# 2019_Dashboard_1-28-19.net
KiCad netlist of a schematic drawn in EAGLE
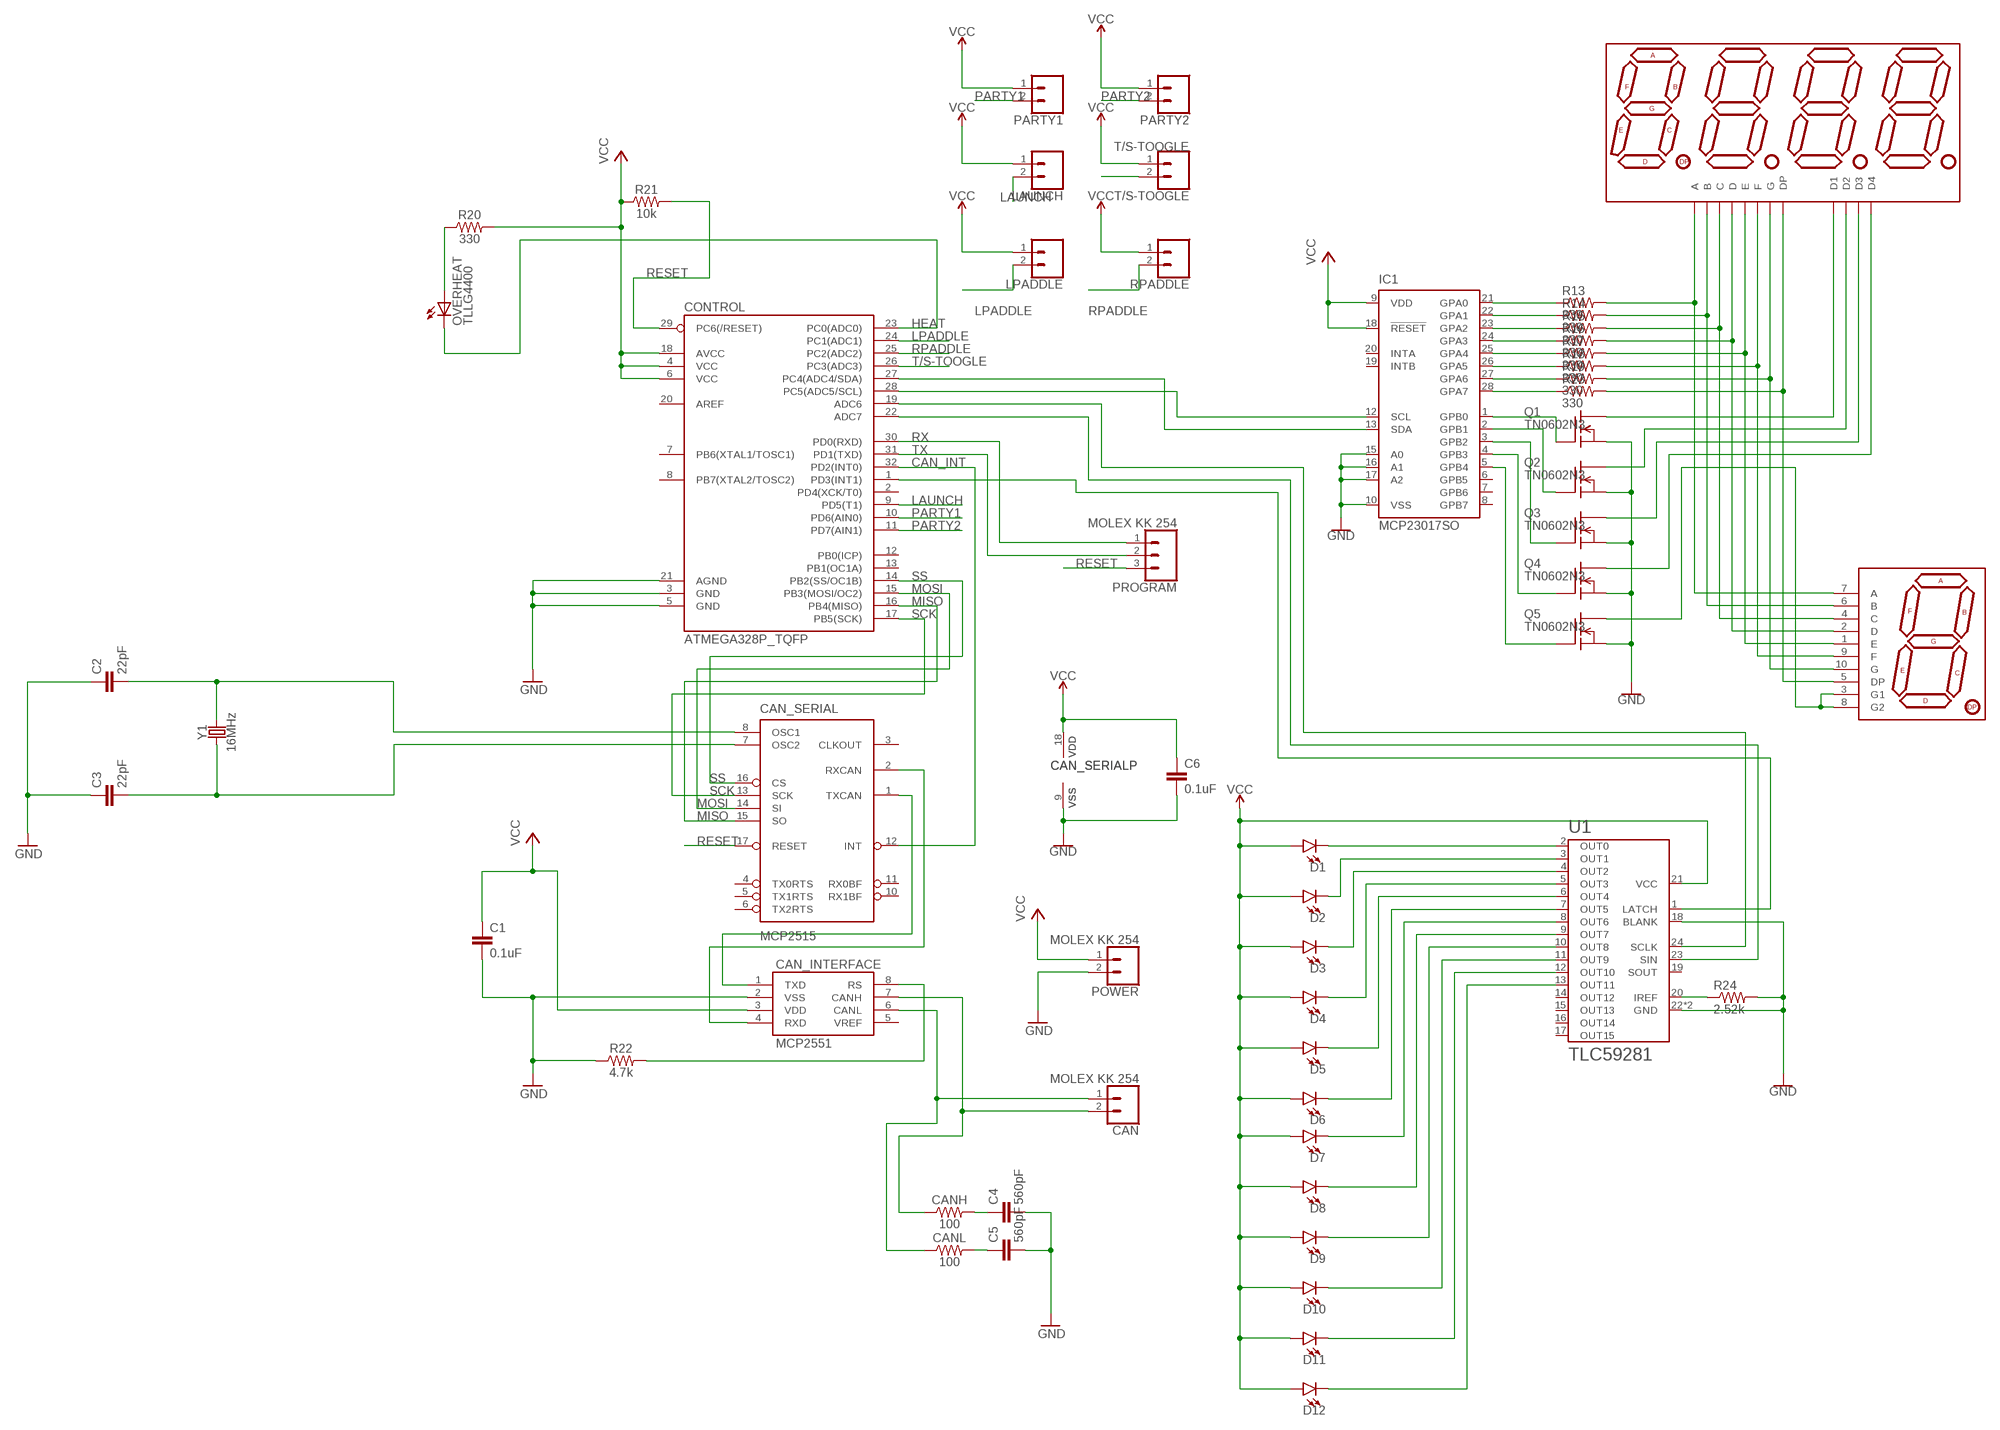
[diagram p0: schematic, sheet 1]

(export (version "E")
  (design (tool "Eeschema 10.0.6"))
  (components
    (comp (ref "C1")
      (value "0.1uF")
      (footprint "eagle-import:0603")
      (libsource (lib "eagle-import") (part "0.1UF-0603-25V-(+80/-20%)"))
    )
    (comp (ref "C2")
      (value "22pF")
      (footprint "eagle-import:0603")
      (libsource (lib "eagle-import") (part "22PF-0603-50V-5%"))
    )
    (comp (ref "C3")
      (value "22pF")
      (footprint "eagle-import:0603")
      (libsource (lib "eagle-import") (part "22PF-0603-50V-5%"))
    )
    (comp (ref "C4")
      (value "560pF")
      (footprint "eagle-import:0603")
      (libsource (lib "eagle-import") (part "560PF-0603-50V-5%"))
    )
    (comp (ref "C5")
      (value "560pF")
      (footprint "eagle-import:0603")
      (libsource (lib "eagle-import") (part "560PF-0603-50V-5%"))
    )
    (comp (ref "C6")
      (value "0.1uF")
      (footprint "eagle-import:0402")
      (libsource (lib "eagle-import") (part "0.1UF-0402-16V-10%"))
    )
    (comp (ref "CAN")
      (value "MOLEX KK 254")
      (footprint "eagle-import:1X02")
      (libsource (lib "eagle-import") (part "CONN_02"))
    )
    (comp (ref "CANH")
      (value "100")
      (footprint "eagle-import:0603")
      (libsource (lib "eagle-import") (part "100OHM-0603-1/4W-5%"))
    )
    (comp (ref "CANL")
      (value "100")
      (footprint "eagle-import:0603")
      (libsource (lib "eagle-import") (part "100OHM-0603-1/4W-5%"))
    )
    (comp (ref "CAN_INTERFACE")
      (value "MCP2551")
      (footprint "eagle-import:SO08")
      (libsource (lib "eagle-import") (part "MCP2551"))
    )
    (comp (ref "CAN_SERIAL")
      (value "MCP2515")
      (footprint "eagle-import:SO18W")
      (libsource (lib "eagle-import") (part "MCP2515(MCP2510)SO"))
    )
    (comp (ref "CONTROL")
      (value "ATMEGA328P_TQFP")
      (footprint "eagle-import:TQFP32-08")
      (libsource (lib "eagle-import") (part "ATMEGA328P_TQFP"))
    )
    (comp (ref "D1")
      (value "LED5MM")
      (footprint "eagle-import:LED_5MM")
      (libsource (lib "eagle-import") (part "LED5MM"))
    )
    (comp (ref "D2")
      (value "LED5MM")
      (footprint "eagle-import:LED_5MM")
      (libsource (lib "eagle-import") (part "LED5MM"))
    )
    (comp (ref "D3")
      (value "LED5MM")
      (footprint "eagle-import:LED_5MM")
      (libsource (lib "eagle-import") (part "LED5MM"))
    )
    (comp (ref "D4")
      (value "LED5MM")
      (footprint "eagle-import:LED_5MM")
      (libsource (lib "eagle-import") (part "LED5MM"))
    )
    (comp (ref "D5")
      (value "LED5MM")
      (footprint "eagle-import:LED_5MM")
      (libsource (lib "eagle-import") (part "LED5MM"))
    )
    (comp (ref "D6")
      (value "LED5MM")
      (footprint "eagle-import:LED_5MM")
      (libsource (lib "eagle-import") (part "LED5MM"))
    )
    (comp (ref "D7")
      (value "LED5MM")
      (footprint "eagle-import:LED_5MM")
      (libsource (lib "eagle-import") (part "LED5MM"))
    )
    (comp (ref "D8")
      (value "LED5MM")
      (footprint "eagle-import:LED_5MM")
      (libsource (lib "eagle-import") (part "LED5MM"))
    )
    (comp (ref "D9")
      (value "LED5MM")
      (footprint "eagle-import:LED_5MM")
      (libsource (lib "eagle-import") (part "LED5MM"))
    )
    (comp (ref "D10")
      (value "LED5MM")
      (footprint "eagle-import:LED_5MM")
      (libsource (lib "eagle-import") (part "LED5MM"))
    )
    (comp (ref "D11")
      (value "LED5MM")
      (footprint "eagle-import:LED_5MM")
      (libsource (lib "eagle-import") (part "LED5MM"))
    )
    (comp (ref "D12")
      (value "LED5MM")
      (footprint "eagle-import:LED_5MM")
      (libsource (lib "eagle-import") (part "LED5MM"))
    )
    (comp (ref "DISP1")
      (value "ATA8041ARBJ")
      (footprint "eagle-import:7-SEGMENT-4DIGIT-20MM")
      (libsource (lib "eagle-import") (part "7-SEGMENT-4DIGIT-20MM-RED"))
    )
    (comp (ref "IC1")
      (value "MCP23017SO")
      (footprint "eagle-import:SO28W")
      (libsource (lib "eagle-import") (part "MCP23017SO"))
    )
    (comp (ref "LAUNCH")
      (value "CONN_02LOCK")
      (footprint "eagle-import:1X02_LOCK")
      (libsource (lib "eagle-import") (part "CONN_02LOCK"))
    )
    (comp (ref "LPADDLE")
      (value "CONN_02LOCK")
      (footprint "eagle-import:1X02_LOCK")
      (libsource (lib "eagle-import") (part "CONN_02LOCK"))
    )
    (comp (ref "OVERHEAT")
      (value "TLLG4400")
      (footprint "eagle-import:LED3MM")
      (fields (field (name "MF") "VISHAY SEMICONDUCTOR"))
      (libsource (lib "eagle-import") (part "TLLG4400"))
    )
    (comp (ref "PARTY1")
      (value "CONN_02LOCK")
      (footprint "eagle-import:1X02_LOCK")
      (libsource (lib "eagle-import") (part "CONN_02LOCK"))
    )
    (comp (ref "PARTY2")
      (value "CONN_02LOCK")
      (footprint "eagle-import:1X02_LOCK")
      (libsource (lib "eagle-import") (part "CONN_02LOCK"))
    )
    (comp (ref "POWER")
      (value "MOLEX KK 254")
      (footprint "eagle-import:1X02")
      (libsource (lib "eagle-import") (part "CONN_02"))
    )
    (comp (ref "PROGRAM")
      (value "MOLEX KK 254")
      (footprint "eagle-import:1X03")
      (libsource (lib "eagle-import") (part "CONN_03"))
    )
    (comp (ref "Q1")
      (value "TN0602N3")
      (footprint "eagle-import:TO-92")
      (libsource (lib "eagle-import") (part "TN0602N3"))
    )
    (comp (ref "Q2")
      (value "TN0602N3")
      (footprint "eagle-import:TO-92")
      (libsource (lib "eagle-import") (part "TN0602N3"))
    )
    (comp (ref "Q3")
      (value "TN0602N3")
      (footprint "eagle-import:TO-92")
      (libsource (lib "eagle-import") (part "TN0602N3"))
    )
    (comp (ref "Q4")
      (value "TN0602N3")
      (footprint "eagle-import:TO-92")
      (libsource (lib "eagle-import") (part "TN0602N3"))
    )
    (comp (ref "Q5")
      (value "TN0602N3")
      (footprint "eagle-import:TO-92")
      (libsource (lib "eagle-import") (part "TN0602N3"))
    )
    (comp (ref "R13")
      (value "330")
      (footprint "eagle-import:R0603")
      (libsource (lib "eagle-import") (part "R-US_R0603"))
    )
    (comp (ref "R14")
      (value "330")
      (footprint "eagle-import:R0603")
      (libsource (lib "eagle-import") (part "R-US_R0603"))
    )
    (comp (ref "R15")
      (value "330")
      (footprint "eagle-import:R0603")
      (libsource (lib "eagle-import") (part "R-US_R0603"))
    )
    (comp (ref "R16")
      (value "330")
      (footprint "eagle-import:R0603")
      (libsource (lib "eagle-import") (part "R-US_R0603"))
    )
    (comp (ref "R17")
      (value "330")
      (footprint "eagle-import:R0603")
      (libsource (lib "eagle-import") (part "R-US_R0603"))
    )
    (comp (ref "R18")
      (value "330")
      (footprint "eagle-import:R0603")
      (libsource (lib "eagle-import") (part "R-US_R0603"))
    )
    (comp (ref "R19")
      (value "330")
      (footprint "eagle-import:R0603")
      (libsource (lib "eagle-import") (part "R-US_R0603"))
    )
    (comp (ref "R20")
      (value "330")
      (footprint "eagle-import:0603")
      (libsource (lib "eagle-import") (part "330OHM-0603-1/10W-1%"))
    )
    (comp (ref "R21")
      (value "10k")
      (footprint "eagle-import:0603")
      (libsource (lib "eagle-import") (part "10KOHM-0603-1/10W-1%"))
    )
    (comp (ref "R22")
      (value "4.7k")
      (footprint "eagle-import:0603")
      (libsource (lib "eagle-import") (part "4.7KOHM-0603-1/10W-1%"))
    )
    (comp (ref "R23")
      (value "330")
      (footprint "eagle-import:R0603")
      (libsource (lib "eagle-import") (part "R-US_R0603"))
    )
    (comp (ref "R24")
      (value "2.52k")
      (footprint "eagle-import:R0603")
      (libsource (lib "eagle-import") (part "R-US_R0603"))
    )
    (comp (ref "RPADDLE")
      (value "CONN_02LOCK")
      (footprint "eagle-import:1X02_LOCK")
      (libsource (lib "eagle-import") (part "CONN_02LOCK"))
    )
    (comp (ref "T/S-TOOGLE")
      (value "CONN_02LOCK")
      (footprint "eagle-import:1X02_LOCK")
      (libsource (lib "eagle-import") (part "CONN_02LOCK"))
    )
    (comp (ref "U$1")
      (value "YSD-1601AR4B-8")
      (footprint "eagle-import:7-SEGMENT-1_PTH")
      (libsource (lib "eagle-import") (part "7-SEGMENT-1DIGIT-1INCH-RED"))
    )
    (comp (ref "U1")
      (value "TLC59281")
      (footprint "eagle-import:QFN-24")
      (fields (field (name "MF") "Texas Instruments"))
      (libsource (lib "eagle-import") (part "TLC59281"))
    )
    (comp (ref "Y1")
      (value "16MHz")
      (footprint "eagle-import:HC49US")
      (libsource (lib "eagle-import") (part "CRYSTAL-16MHZPTH-HC49US"))
    )
  )
  (nets
    (net (code "1") (name "/CAN_INT") (class "Default")
      (node (ref "CAN_SERIAL") (pin "12") (pinfunction "INT_12") (pintype "output"))
      (node (ref "CONTROL") (pin "32") (pinfunction "PD2(INT0)_32") (pintype "bidirectional"))
    )
    (net (code "2") (name "/HEAT") (class "Default")
      (node (ref "CONTROL") (pin "23") (pinfunction "PC0(ADC0)_23") (pintype "bidirectional"))
      (node (ref "OVERHEAT") (pin "K") (pinfunction "C_K") (pintype "passive"))
    )
    (net (code "3") (name "/LAUNCH") (class "Default")
      (node (ref "CONTROL") (pin "9") (pinfunction "PD5(T1)_9") (pintype "bidirectional"))
      (node (ref "LAUNCH") (pin "2") (pinfunction "2_2") (pintype "passive"))
    )
    (net (code "4") (name "/LPADDLE") (class "Default")
      (node (ref "CONTROL") (pin "24") (pinfunction "PC1(ADC1)_24") (pintype "bidirectional"))
      (node (ref "LPADDLE") (pin "2") (pinfunction "2_2") (pintype "passive"))
    )
    (net (code "5") (name "/MISO") (class "Default")
      (node (ref "CAN_SERIAL") (pin "15") (pinfunction "SO_15") (pintype "output"))
      (node (ref "CONTROL") (pin "16") (pinfunction "PB4(MISO)_16") (pintype "bidirectional"))
    )
    (net (code "6") (name "/MOSI") (class "Default")
      (node (ref "CAN_SERIAL") (pin "14") (pinfunction "SI_14") (pintype "input"))
      (node (ref "CONTROL") (pin "15") (pinfunction "PB3(MOSI/OC2)_15") (pintype "bidirectional"))
    )
    (net (code "7") (name "/PARTY1") (class "Default")
      (node (ref "CONTROL") (pin "10") (pinfunction "PD6(AIN0)_10") (pintype "bidirectional"))
      (node (ref "PARTY1") (pin "2") (pinfunction "2_2") (pintype "passive"))
    )
    (net (code "8") (name "/PARTY2") (class "Default")
      (node (ref "CONTROL") (pin "11") (pinfunction "PD7(AIN1)_11") (pintype "bidirectional"))
      (node (ref "PARTY2") (pin "2") (pinfunction "2_2") (pintype "passive"))
    )
    (net (code "9") (name "/RESET") (class "Default")
      (node (ref "CAN_SERIAL") (pin "17") (pinfunction "RESET_17") (pintype "input"))
      (node (ref "CONTROL") (pin "29") (pinfunction "PC6(/RESET)_29") (pintype "bidirectional"))
      (node (ref "PROGRAM") (pin "3") (pinfunction "3_3") (pintype "passive"))
      (node (ref "R21") (pin "2") (pinfunction "2_2") (pintype "passive"))
    )
    (net (code "10") (name "/RPADDLE") (class "Default")
      (node (ref "CONTROL") (pin "25") (pinfunction "PC2(ADC2)_25") (pintype "bidirectional"))
      (node (ref "RPADDLE") (pin "2") (pinfunction "2_2") (pintype "passive"))
    )
    (net (code "11") (name "/RX") (class "Default")
      (node (ref "CONTROL") (pin "30") (pinfunction "PD0(RXD)_30") (pintype "bidirectional"))
      (node (ref "PROGRAM") (pin "1") (pinfunction "1_1") (pintype "passive"))
    )
    (net (code "12") (name "/SCK") (class "Default")
      (node (ref "CAN_SERIAL") (pin "13") (pinfunction "SCK_13") (pintype "input"))
      (node (ref "CONTROL") (pin "17") (pinfunction "PB5(SCK)_17") (pintype "bidirectional"))
    )
    (net (code "13") (name "/SS") (class "Default")
      (node (ref "CAN_SERIAL") (pin "16") (pinfunction "CS_16") (pintype "input"))
      (node (ref "CONTROL") (pin "14") (pinfunction "PB2(SS/OC1B)_14") (pintype "bidirectional"))
    )
    (net (code "14") (name "/TX") (class "Default")
      (node (ref "CONTROL") (pin "31") (pinfunction "PD1(TXD)_31") (pintype "bidirectional"))
      (node (ref "PROGRAM") (pin "2") (pinfunction "2_2") (pintype "passive"))
    )
    (net (code "15") (name "/T{slash}S-TOOGLE") (class "Default")
      (node (ref "CONTROL") (pin "26") (pinfunction "PC3(ADC3)_26") (pintype "bidirectional"))
      (node (ref "T/S-TOOGLE") (pin "2") (pinfunction "2_2") (pintype "passive"))
    )
    (net (code "16") (name "GND") (class "Default")
      (node (ref "C1") (pin "2") (pinfunction "2_2") (pintype "passive"))
      (node (ref "C2") (pin "1") (pinfunction "1_1") (pintype "passive"))
      (node (ref "C3") (pin "1") (pinfunction "1_1") (pintype "passive"))
      (node (ref "C4") (pin "2") (pinfunction "2_2") (pintype "passive"))
      (node (ref "C5") (pin "2") (pinfunction "2_2") (pintype "passive"))
      (node (ref "C6") (pin "2") (pinfunction "2_2") (pintype "passive"))
      (node (ref "CAN_INTERFACE") (pin "2") (pinfunction "VSS_2") (pintype "bidirectional"))
      (node (ref "CAN_SERIAL") (pin "9") (pinfunction "VSS_9") (pintype "power_in"))
      (node (ref "CONTROL") (pin "21") (pinfunction "AGND_21") (pintype "bidirectional"))
      (node (ref "CONTROL") (pin "3") (pinfunction "GND_3") (pintype "bidirectional"))
      (node (ref "CONTROL") (pin "5") (pinfunction "GND_5") (pintype "bidirectional"))
      (node (ref "IC1") (pin "10") (pinfunction "VSS_10") (pintype "power_in"))
      (node (ref "IC1") (pin "15") (pinfunction "A0_15") (pintype "input"))
      (node (ref "IC1") (pin "16") (pinfunction "A1_16") (pintype "input"))
      (node (ref "IC1") (pin "17") (pinfunction "A2_17") (pintype "input"))
      (node (ref "POWER") (pin "2") (pinfunction "2_2") (pintype "passive"))
      (node (ref "Q1") (pin "1") (pinfunction "S_1") (pintype "passive"))
      (node (ref "Q2") (pin "1") (pinfunction "S_1") (pintype "passive"))
      (node (ref "Q3") (pin "1") (pinfunction "S_1") (pintype "passive"))
      (node (ref "Q4") (pin "1") (pinfunction "S_1") (pintype "passive"))
      (node (ref "Q5") (pin "1") (pinfunction "S_1") (pintype "passive"))
      (node (ref "R22") (pin "1") (pinfunction "1_1") (pintype "passive"))
      (node (ref "R24") (pin "2") (pinfunction "2_2") (pintype "passive"))
      (node (ref "U1") (pin "18") (pinfunction "BLANK_18") (pintype "bidirectional"))
      (node (ref "U1") (pin "22") (pinfunction "GND_22") (pintype "bidirectional"))
      (node (ref "U1") (pin "EP") (pinfunction "GND_EP") (pintype "bidirectional"))
    )
    (net (code "17") (name "Net-(C4-Pad1)") (class "Default")
      (node (ref "C4") (pin "1") (pinfunction "1_1") (pintype "passive"))
      (node (ref "CANH") (pin "2") (pinfunction "2_2") (pintype "passive"))
    )
    (net (code "18") (name "Net-(C5-Pad1)") (class "Default")
      (node (ref "C5") (pin "1") (pinfunction "1_1") (pintype "passive"))
      (node (ref "CANL") (pin "2") (pinfunction "2_2") (pintype "passive"))
    )
    (net (code "19") (name "Net-(CAN_INTERFACE-CANH)") (class "Default")
      (node (ref "CAN") (pin "2") (pinfunction "2_2") (pintype "passive"))
      (node (ref "CANH") (pin "1") (pinfunction "1_1") (pintype "passive"))
      (node (ref "CAN_INTERFACE") (pin "7") (pinfunction "CANH_7") (pintype "bidirectional"))
    )
    (net (code "20") (name "Net-(CAN_INTERFACE-CANL)") (class "Default")
      (node (ref "CAN") (pin "1") (pinfunction "1_1") (pintype "passive"))
      (node (ref "CANL") (pin "1") (pinfunction "1_1") (pintype "passive"))
      (node (ref "CAN_INTERFACE") (pin "6") (pinfunction "CANL_6") (pintype "bidirectional"))
    )
    (net (code "21") (name "Net-(CAN_INTERFACE-RS)") (class "Default")
      (node (ref "CAN_INTERFACE") (pin "8") (pinfunction "RS_8") (pintype "bidirectional"))
      (node (ref "R22") (pin "2") (pinfunction "2_2") (pintype "passive"))
    )
    (net (code "22") (name "Net-(CAN_INTERFACE-RXD)") (class "Default")
      (node (ref "CAN_INTERFACE") (pin "4") (pinfunction "RXD_4") (pintype "bidirectional"))
      (node (ref "CAN_SERIAL") (pin "2") (pinfunction "RXCAN_2") (pintype "input"))
    )
    (net (code "23") (name "Net-(CAN_INTERFACE-TXD)") (class "Default")
      (node (ref "CAN_INTERFACE") (pin "1") (pinfunction "TXD_1") (pintype "bidirectional"))
      (node (ref "CAN_SERIAL") (pin "1") (pinfunction "TXCAN_1") (pintype "output"))
    )
    (net (code "24") (name "Net-(CAN_SERIALA-OSC1)") (class "Default")
      (node (ref "C2") (pin "2") (pinfunction "2_2") (pintype "passive"))
      (node (ref "CAN_SERIAL") (pin "8") (pinfunction "OSC1_8") (pintype "input"))
      (node (ref "Y1") (pin "2") (pinfunction "2_2") (pintype "passive"))
    )
    (net (code "25") (name "Net-(CAN_SERIALA-OSC2)") (class "Default")
      (node (ref "C3") (pin "2") (pinfunction "2_2") (pintype "passive"))
      (node (ref "CAN_SERIAL") (pin "7") (pinfunction "OSC2_7") (pintype "output"))
      (node (ref "Y1") (pin "1") (pinfunction "1_1") (pintype "passive"))
    )
    (net (code "26") (name "Net-(CONTROL-ADC6)") (class "Default")
      (node (ref "CONTROL") (pin "19") (pinfunction "ADC6_19") (pintype "bidirectional"))
      (node (ref "U1") (pin "24") (pinfunction "SCLK_24") (pintype "bidirectional"))
    )
    (net (code "27") (name "Net-(CONTROL-ADC7)") (class "Default")
      (node (ref "CONTROL") (pin "22") (pinfunction "ADC7_22") (pintype "bidirectional"))
      (node (ref "U1") (pin "23") (pinfunction "SIN_23") (pintype "bidirectional"))
    )
    (net (code "28") (name "Net-(CONTROL-PC4(ADC4{slash}SDA))") (class "Default")
      (node (ref "CONTROL") (pin "27") (pinfunction "PC4(ADC4/SDA)_27") (pintype "bidirectional"))
      (node (ref "IC1") (pin "13") (pinfunction "SDA_13") (pintype "bidirectional"))
    )
    (net (code "29") (name "Net-(CONTROL-PC5(ADC5{slash}SCL))") (class "Default")
      (node (ref "CONTROL") (pin "28") (pinfunction "PC5(ADC5/SCL)_28") (pintype "bidirectional"))
      (node (ref "IC1") (pin "12") (pinfunction "SCL_12") (pintype "input"))
    )
    (net (code "30") (name "Net-(CONTROL-PD3(INT1))") (class "Default")
      (node (ref "CONTROL") (pin "1") (pinfunction "PD3(INT1)_1") (pintype "bidirectional"))
      (node (ref "U1") (pin "1") (pinfunction "LATCH_1") (pintype "bidirectional"))
    )
    (net (code "31") (name "Net-(D1-C)") (class "Default")
      (node (ref "D1") (pin "K") (pinfunction "C_K") (pintype "passive"))
      (node (ref "U1") (pin "2") (pinfunction "OUT0_2") (pintype "bidirectional"))
    )
    (net (code "32") (name "Net-(D2-C)") (class "Default")
      (node (ref "D2") (pin "K") (pinfunction "C_K") (pintype "passive"))
      (node (ref "U1") (pin "3") (pinfunction "OUT1_3") (pintype "bidirectional"))
    )
    (net (code "33") (name "Net-(D3-C)") (class "Default")
      (node (ref "D3") (pin "K") (pinfunction "C_K") (pintype "passive"))
      (node (ref "U1") (pin "4") (pinfunction "OUT2_4") (pintype "bidirectional"))
    )
    (net (code "34") (name "Net-(D4-C)") (class "Default")
      (node (ref "D4") (pin "K") (pinfunction "C_K") (pintype "passive"))
      (node (ref "U1") (pin "5") (pinfunction "OUT3_5") (pintype "bidirectional"))
    )
    (net (code "35") (name "Net-(D5-C)") (class "Default")
      (node (ref "D5") (pin "K") (pinfunction "C_K") (pintype "passive"))
      (node (ref "U1") (pin "6") (pinfunction "OUT4_6") (pintype "bidirectional"))
    )
    (net (code "36") (name "Net-(D6-C)") (class "Default")
      (node (ref "D6") (pin "K") (pinfunction "C_K") (pintype "passive"))
      (node (ref "U1") (pin "7") (pinfunction "OUT5_7") (pintype "bidirectional"))
    )
    (net (code "37") (name "Net-(D7-C)") (class "Default")
      (node (ref "D7") (pin "K") (pinfunction "C_K") (pintype "passive"))
      (node (ref "U1") (pin "8") (pinfunction "OUT6_8") (pintype "bidirectional"))
    )
    (net (code "38") (name "Net-(D8-C)") (class "Default")
      (node (ref "D8") (pin "K") (pinfunction "C_K") (pintype "passive"))
      (node (ref "U1") (pin "9") (pinfunction "OUT7_9") (pintype "bidirectional"))
    )
    (net (code "39") (name "Net-(D9-C)") (class "Default")
      (node (ref "D9") (pin "K") (pinfunction "C_K") (pintype "passive"))
      (node (ref "U1") (pin "10") (pinfunction "OUT8_10") (pintype "bidirectional"))
    )
    (net (code "40") (name "Net-(D10-C)") (class "Default")
      (node (ref "D10") (pin "K") (pinfunction "C_K") (pintype "passive"))
      (node (ref "U1") (pin "11") (pinfunction "OUT9_11") (pintype "bidirectional"))
    )
    (net (code "41") (name "Net-(D11-C)") (class "Default")
      (node (ref "D11") (pin "K") (pinfunction "C_K") (pintype "passive"))
      (node (ref "U1") (pin "12") (pinfunction "OUT10_12") (pintype "bidirectional"))
    )
    (net (code "42") (name "Net-(D12-C)") (class "Default")
      (node (ref "D12") (pin "K") (pinfunction "C_K") (pintype "passive"))
      (node (ref "U1") (pin "13") (pinfunction "OUT11_13") (pintype "bidirectional"))
    )
    (net (code "43") (name "Net-(DISP1-A)") (class "Default")
      (node (ref "DISP1") (pin "11") (pinfunction "A_11") (pintype "bidirectional"))
      (node (ref "R13") (pin "2") (pinfunction "2_2") (pintype "passive"))
      (node (ref "U$1") (pin "7") (pinfunction "A_7") (pintype "bidirectional"))
    )
    (net (code "44") (name "Net-(DISP1-B)") (class "Default")
      (node (ref "DISP1") (pin "7") (pinfunction "B_7") (pintype "bidirectional"))
      (node (ref "R14") (pin "2") (pinfunction "2_2") (pintype "passive"))
      (node (ref "U$1") (pin "6") (pinfunction "B_6") (pintype "bidirectional"))
    )
    (net (code "45") (name "Net-(DISP1-C)") (class "Default")
      (node (ref "DISP1") (pin "4") (pinfunction "C_4") (pintype "bidirectional"))
      (node (ref "R15") (pin "2") (pinfunction "2_2") (pintype "passive"))
      (node (ref "U$1") (pin "4") (pinfunction "C_4") (pintype "bidirectional"))
    )
    (net (code "46") (name "Net-(DISP1-D)") (class "Default")
      (node (ref "DISP1") (pin "2") (pinfunction "D_2") (pintype "bidirectional"))
      (node (ref "R16") (pin "2") (pinfunction "2_2") (pintype "passive"))
      (node (ref "U$1") (pin "2") (pinfunction "D_2") (pintype "bidirectional"))
    )
    (net (code "47") (name "Net-(DISP1-D1)") (class "Default")
      (node (ref "DISP1") (pin "12") (pinfunction "D1_12") (pintype "bidirectional"))
      (node (ref "Q1") (pin "3") (pinfunction "D_3") (pintype "passive"))
    )
    (net (code "48") (name "Net-(DISP1-D2)") (class "Default")
      (node (ref "DISP1") (pin "9") (pinfunction "D2_9") (pintype "bidirectional"))
      (node (ref "Q2") (pin "3") (pinfunction "D_3") (pintype "passive"))
    )
    (net (code "49") (name "Net-(DISP1-D3)") (class "Default")
      (node (ref "DISP1") (pin "8") (pinfunction "D3_8") (pintype "bidirectional"))
      (node (ref "Q3") (pin "3") (pinfunction "D_3") (pintype "passive"))
    )
    (net (code "50") (name "Net-(DISP1-D4)") (class "Default")
      (node (ref "DISP1") (pin "6") (pinfunction "D4_6") (pintype "bidirectional"))
      (node (ref "Q4") (pin "3") (pinfunction "D_3") (pintype "passive"))
    )
    (net (code "51") (name "Net-(DISP1-DP)") (class "Default")
      (node (ref "DISP1") (pin "3") (pinfunction "DP_3") (pintype "bidirectional"))
      (node (ref "R23") (pin "2") (pinfunction "2_2") (pintype "passive"))
      (node (ref "U$1") (pin "5") (pinfunction "DP_5") (pintype "bidirectional"))
    )
    (net (code "52") (name "Net-(DISP1-E)") (class "Default")
      (node (ref "DISP1") (pin "1") (pinfunction "E_1") (pintype "bidirectional"))
      (node (ref "R17") (pin "2") (pinfunction "2_2") (pintype "passive"))
      (node (ref "U$1") (pin "1") (pinfunction "E_1") (pintype "bidirectional"))
    )
    (net (code "53") (name "Net-(DISP1-F)") (class "Default")
      (node (ref "DISP1") (pin "10") (pinfunction "F_10") (pintype "bidirectional"))
      (node (ref "R18") (pin "2") (pinfunction "2_2") (pintype "passive"))
      (node (ref "U$1") (pin "9") (pinfunction "F_9") (pintype "bidirectional"))
    )
    (net (code "54") (name "Net-(DISP1-G)") (class "Default")
      (node (ref "DISP1") (pin "5") (pinfunction "G_5") (pintype "bidirectional"))
      (node (ref "R19") (pin "2") (pinfunction "2_2") (pintype "passive"))
      (node (ref "U$1") (pin "10") (pinfunction "G_10") (pintype "bidirectional"))
    )
    (net (code "55") (name "Net-(IC1-GPA0)") (class "Default")
      (node (ref "IC1") (pin "21") (pinfunction "GPA0_21") (pintype "bidirectional"))
      (node (ref "R13") (pin "1") (pinfunction "1_1") (pintype "passive"))
    )
    (net (code "56") (name "Net-(IC1-GPA1)") (class "Default")
      (node (ref "IC1") (pin "22") (pinfunction "GPA1_22") (pintype "bidirectional"))
      (node (ref "R14") (pin "1") (pinfunction "1_1") (pintype "passive"))
    )
    (net (code "57") (name "Net-(IC1-GPA2)") (class "Default")
      (node (ref "IC1") (pin "23") (pinfunction "GPA2_23") (pintype "bidirectional"))
      (node (ref "R15") (pin "1") (pinfunction "1_1") (pintype "passive"))
    )
    (net (code "58") (name "Net-(IC1-GPA3)") (class "Default")
      (node (ref "IC1") (pin "24") (pinfunction "GPA3_24") (pintype "bidirectional"))
      (node (ref "R16") (pin "1") (pinfunction "1_1") (pintype "passive"))
    )
    (net (code "59") (name "Net-(IC1-GPA4)") (class "Default")
      (node (ref "IC1") (pin "25") (pinfunction "GPA4_25") (pintype "bidirectional"))
      (node (ref "R17") (pin "1") (pinfunction "1_1") (pintype "passive"))
    )
    (net (code "60") (name "Net-(IC1-GPA5)") (class "Default")
      (node (ref "IC1") (pin "26") (pinfunction "GPA5_26") (pintype "bidirectional"))
      (node (ref "R18") (pin "1") (pinfunction "1_1") (pintype "passive"))
    )
    (net (code "61") (name "Net-(IC1-GPA6)") (class "Default")
      (node (ref "IC1") (pin "27") (pinfunction "GPA6_27") (pintype "bidirectional"))
      (node (ref "R19") (pin "1") (pinfunction "1_1") (pintype "passive"))
    )
    (net (code "62") (name "Net-(IC1-GPA7)") (class "Default")
      (node (ref "IC1") (pin "28") (pinfunction "GPA7_28") (pintype "bidirectional"))
      (node (ref "R23") (pin "1") (pinfunction "1_1") (pintype "passive"))
    )
    (net (code "63") (name "Net-(IC1-GPB0)") (class "Default")
      (node (ref "IC1") (pin "1") (pinfunction "GPB0_1") (pintype "bidirectional"))
      (node (ref "Q1") (pin "2") (pinfunction "G_2") (pintype "passive"))
    )
    (net (code "64") (name "Net-(IC1-GPB1)") (class "Default")
      (node (ref "IC1") (pin "2") (pinfunction "GPB1_2") (pintype "bidirectional"))
      (node (ref "Q2") (pin "2") (pinfunction "G_2") (pintype "passive"))
    )
    (net (code "65") (name "Net-(IC1-GPB2)") (class "Default")
      (node (ref "IC1") (pin "3") (pinfunction "GPB2_3") (pintype "bidirectional"))
      (node (ref "Q3") (pin "2") (pinfunction "G_2") (pintype "passive"))
    )
    (net (code "66") (name "Net-(IC1-GPB3)") (class "Default")
      (node (ref "IC1") (pin "4") (pinfunction "GPB3_4") (pintype "bidirectional"))
      (node (ref "Q4") (pin "2") (pinfunction "G_2") (pintype "passive"))
    )
    (net (code "67") (name "Net-(IC1-GPB4)") (class "Default")
      (node (ref "IC1") (pin "5") (pinfunction "GPB4_5") (pintype "bidirectional"))
      (node (ref "Q5") (pin "2") (pinfunction "G_2") (pintype "passive"))
    )
    (net (code "68") (name "Net-(OVERHEAT-PadA)") (class "Default")
      (node (ref "OVERHEAT") (pin "A") (pinfunction "A_A") (pintype "passive"))
      (node (ref "R20") (pin "1") (pinfunction "1_1") (pintype "passive"))
    )
    (net (code "69") (name "Net-(Q5-D)") (class "Default")
      (node (ref "Q5") (pin "3") (pinfunction "D_3") (pintype "passive"))
      (node (ref "U$1") (pin "3") (pinfunction "G1_3") (pintype "bidirectional"))
      (node (ref "U$1") (pin "8") (pinfunction "G2_8") (pintype "bidirectional"))
    )
    (net (code "70") (name "Net-(U1-IREF)") (class "Default")
      (node (ref "R24") (pin "1") (pinfunction "1_1") (pintype "passive"))
      (node (ref "U1") (pin "20") (pinfunction "IREF_20") (pintype "bidirectional"))
    )
    (net (code "71") (name "VCC") (class "Default")
      (node (ref "C1") (pin "1") (pinfunction "1_1") (pintype "passive"))
      (node (ref "C6") (pin "1") (pinfunction "1_1") (pintype "passive"))
      (node (ref "CAN_INTERFACE") (pin "3") (pinfunction "VDD_3") (pintype "bidirectional"))
      (node (ref "CAN_SERIAL") (pin "18") (pinfunction "VDD_18") (pintype "power_in"))
      (node (ref "CONTROL") (pin "18") (pinfunction "AVCC_18") (pintype "bidirectional"))
      (node (ref "CONTROL") (pin "4") (pinfunction "VCC_4") (pintype "bidirectional"))
      (node (ref "CONTROL") (pin "6") (pinfunction "VCC_6") (pintype "bidirectional"))
      (node (ref "D1") (pin "A") (pinfunction "A_A") (pintype "passive"))
      (node (ref "D10") (pin "A") (pinfunction "A_A") (pintype "passive"))
      (node (ref "D11") (pin "A") (pinfunction "A_A") (pintype "passive"))
      (node (ref "D12") (pin "A") (pinfunction "A_A") (pintype "passive"))
      (node (ref "D2") (pin "A") (pinfunction "A_A") (pintype "passive"))
      (node (ref "D3") (pin "A") (pinfunction "A_A") (pintype "passive"))
      (node (ref "D4") (pin "A") (pinfunction "A_A") (pintype "passive"))
      (node (ref "D5") (pin "A") (pinfunction "A_A") (pintype "passive"))
      (node (ref "D6") (pin "A") (pinfunction "A_A") (pintype "passive"))
      (node (ref "D7") (pin "A") (pinfunction "A_A") (pintype "passive"))
      (node (ref "D8") (pin "A") (pinfunction "A_A") (pintype "passive"))
      (node (ref "D9") (pin "A") (pinfunction "A_A") (pintype "passive"))
      (node (ref "IC1") (pin "18") (pinfunction "~{RESET}_18") (pintype "input"))
      (node (ref "IC1") (pin "9") (pinfunction "VDD_9") (pintype "power_in"))
      (node (ref "LAUNCH") (pin "1") (pinfunction "1_1") (pintype "passive"))
      (node (ref "LPADDLE") (pin "1") (pinfunction "1_1") (pintype "passive"))
      (node (ref "PARTY1") (pin "1") (pinfunction "1_1") (pintype "passive"))
      (node (ref "PARTY2") (pin "1") (pinfunction "1_1") (pintype "passive"))
      (node (ref "POWER") (pin "1") (pinfunction "1_1") (pintype "passive"))
      (node (ref "R20") (pin "2") (pinfunction "2_2") (pintype "passive"))
      (node (ref "R21") (pin "1") (pinfunction "1_1") (pintype "passive"))
      (node (ref "RPADDLE") (pin "1") (pinfunction "1_1") (pintype "passive"))
      (node (ref "T/S-TOOGLE") (pin "1") (pinfunction "1_1") (pintype "passive"))
      (node (ref "U1") (pin "21") (pinfunction "VCC_21") (pintype "bidirectional"))
    )
    (net (code "72") (name "unconnected-(CAN_INTERFACE-VREF-Pad5)") (class "Default")
      (node (ref "CAN_INTERFACE") (pin "5") (pinfunction "VREF_5") (pintype "bidirectional"))
    )
    (net (code "73") (name "unconnected-(CAN_SERIALA-CLKOUT-Pad3)") (class "Default")
      (node (ref "CAN_SERIAL") (pin "3") (pinfunction "CLKOUT_3") (pintype "output"))
    )
    (net (code "74") (name "unconnected-(CAN_SERIALA-RX0BF-Pad11)") (class "Default")
      (node (ref "CAN_SERIAL") (pin "11") (pinfunction "RX0BF_11") (pintype "output"))
    )
    (net (code "75") (name "unconnected-(CAN_SERIALA-RX1BF-Pad10)") (class "Default")
      (node (ref "CAN_SERIAL") (pin "10") (pinfunction "RX1BF_10") (pintype "output"))
    )
    (net (code "76") (name "unconnected-(CAN_SERIALA-TX0RTS-Pad4)") (class "Default")
      (node (ref "CAN_SERIAL") (pin "4") (pinfunction "TX0RTS_4") (pintype "input"))
    )
    (net (code "77") (name "unconnected-(CAN_SERIALA-TX1RTS-Pad5)") (class "Default")
      (node (ref "CAN_SERIAL") (pin "5") (pinfunction "TX1RTS_5") (pintype "input"))
    )
    (net (code "78") (name "unconnected-(CAN_SERIALA-TX2RTS-Pad6)") (class "Default")
      (node (ref "CAN_SERIAL") (pin "6") (pinfunction "TX2RTS_6") (pintype "input"))
    )
    (net (code "79") (name "unconnected-(CONTROL-AREF-Pad20)") (class "Default")
      (node (ref "CONTROL") (pin "20") (pinfunction "AREF_20") (pintype "bidirectional"))
    )
    (net (code "80") (name "unconnected-(CONTROL-PB0(ICP)-Pad12)") (class "Default")
      (node (ref "CONTROL") (pin "12") (pinfunction "PB0(ICP)_12") (pintype "bidirectional"))
    )
    (net (code "81") (name "unconnected-(CONTROL-PB1(OC1A)-Pad13)") (class "Default")
      (node (ref "CONTROL") (pin "13") (pinfunction "PB1(OC1A)_13") (pintype "bidirectional"))
    )
    (net (code "82") (name "unconnected-(CONTROL-PB6(XTAL1{slash}TOSC1)-Pad7)") (class "Default")
      (node (ref "CONTROL") (pin "7") (pinfunction "PB6(XTAL1/TOSC1)_7") (pintype "bidirectional"))
    )
    (net (code "83") (name "unconnected-(CONTROL-PB7(XTAL2{slash}TOSC2)-Pad8)") (class "Default")
      (node (ref "CONTROL") (pin "8") (pinfunction "PB7(XTAL2/TOSC2)_8") (pintype "bidirectional"))
    )
    (net (code "84") (name "unconnected-(CONTROL-PD4(XCK{slash}T0)-Pad2)") (class "Default")
      (node (ref "CONTROL") (pin "2") (pinfunction "PD4(XCK/T0)_2") (pintype "bidirectional"))
    )
    (net (code "85") (name "unconnected-(IC1-GPB5-Pad6)") (class "Default")
      (node (ref "IC1") (pin "6") (pinfunction "GPB5_6") (pintype "bidirectional"))
    )
    (net (code "86") (name "unconnected-(IC1-GPB6-Pad7)") (class "Default")
      (node (ref "IC1") (pin "7") (pinfunction "GPB6_7") (pintype "bidirectional"))
    )
    (net (code "87") (name "unconnected-(IC1-GPB7-Pad8)") (class "Default")
      (node (ref "IC1") (pin "8") (pinfunction "GPB7_8") (pintype "bidirectional"))
    )
    (net (code "88") (name "unconnected-(IC1-INTA-Pad20)") (class "Default")
      (node (ref "IC1") (pin "20") (pinfunction "INTA_20") (pintype "output"))
    )
    (net (code "89") (name "unconnected-(IC1-INTB-Pad19)") (class "Default")
      (node (ref "IC1") (pin "19") (pinfunction "INTB_19") (pintype "output"))
    )
    (net (code "90") (name "unconnected-(U1-OUT12-Pad14)") (class "Default")
      (node (ref "U1") (pin "14") (pinfunction "OUT12_14") (pintype "bidirectional"))
    )
    (net (code "91") (name "unconnected-(U1-OUT13-Pad15)") (class "Default")
      (node (ref "U1") (pin "15") (pinfunction "OUT13_15") (pintype "bidirectional"))
    )
    (net (code "92") (name "unconnected-(U1-OUT14-Pad16)") (class "Default")
      (node (ref "U1") (pin "16") (pinfunction "OUT14_16") (pintype "bidirectional"))
    )
    (net (code "93") (name "unconnected-(U1-OUT15-Pad17)") (class "Default")
      (node (ref "U1") (pin "17") (pinfunction "OUT15_17") (pintype "bidirectional"))
    )
    (net (code "94") (name "unconnected-(U1-SOUT-Pad19)") (class "Default")
      (node (ref "U1") (pin "19") (pinfunction "SOUT_19") (pintype "bidirectional"))
    )
  )
)
